# ad.net
KiCad netlist of a schematic drawn in Altium Designer
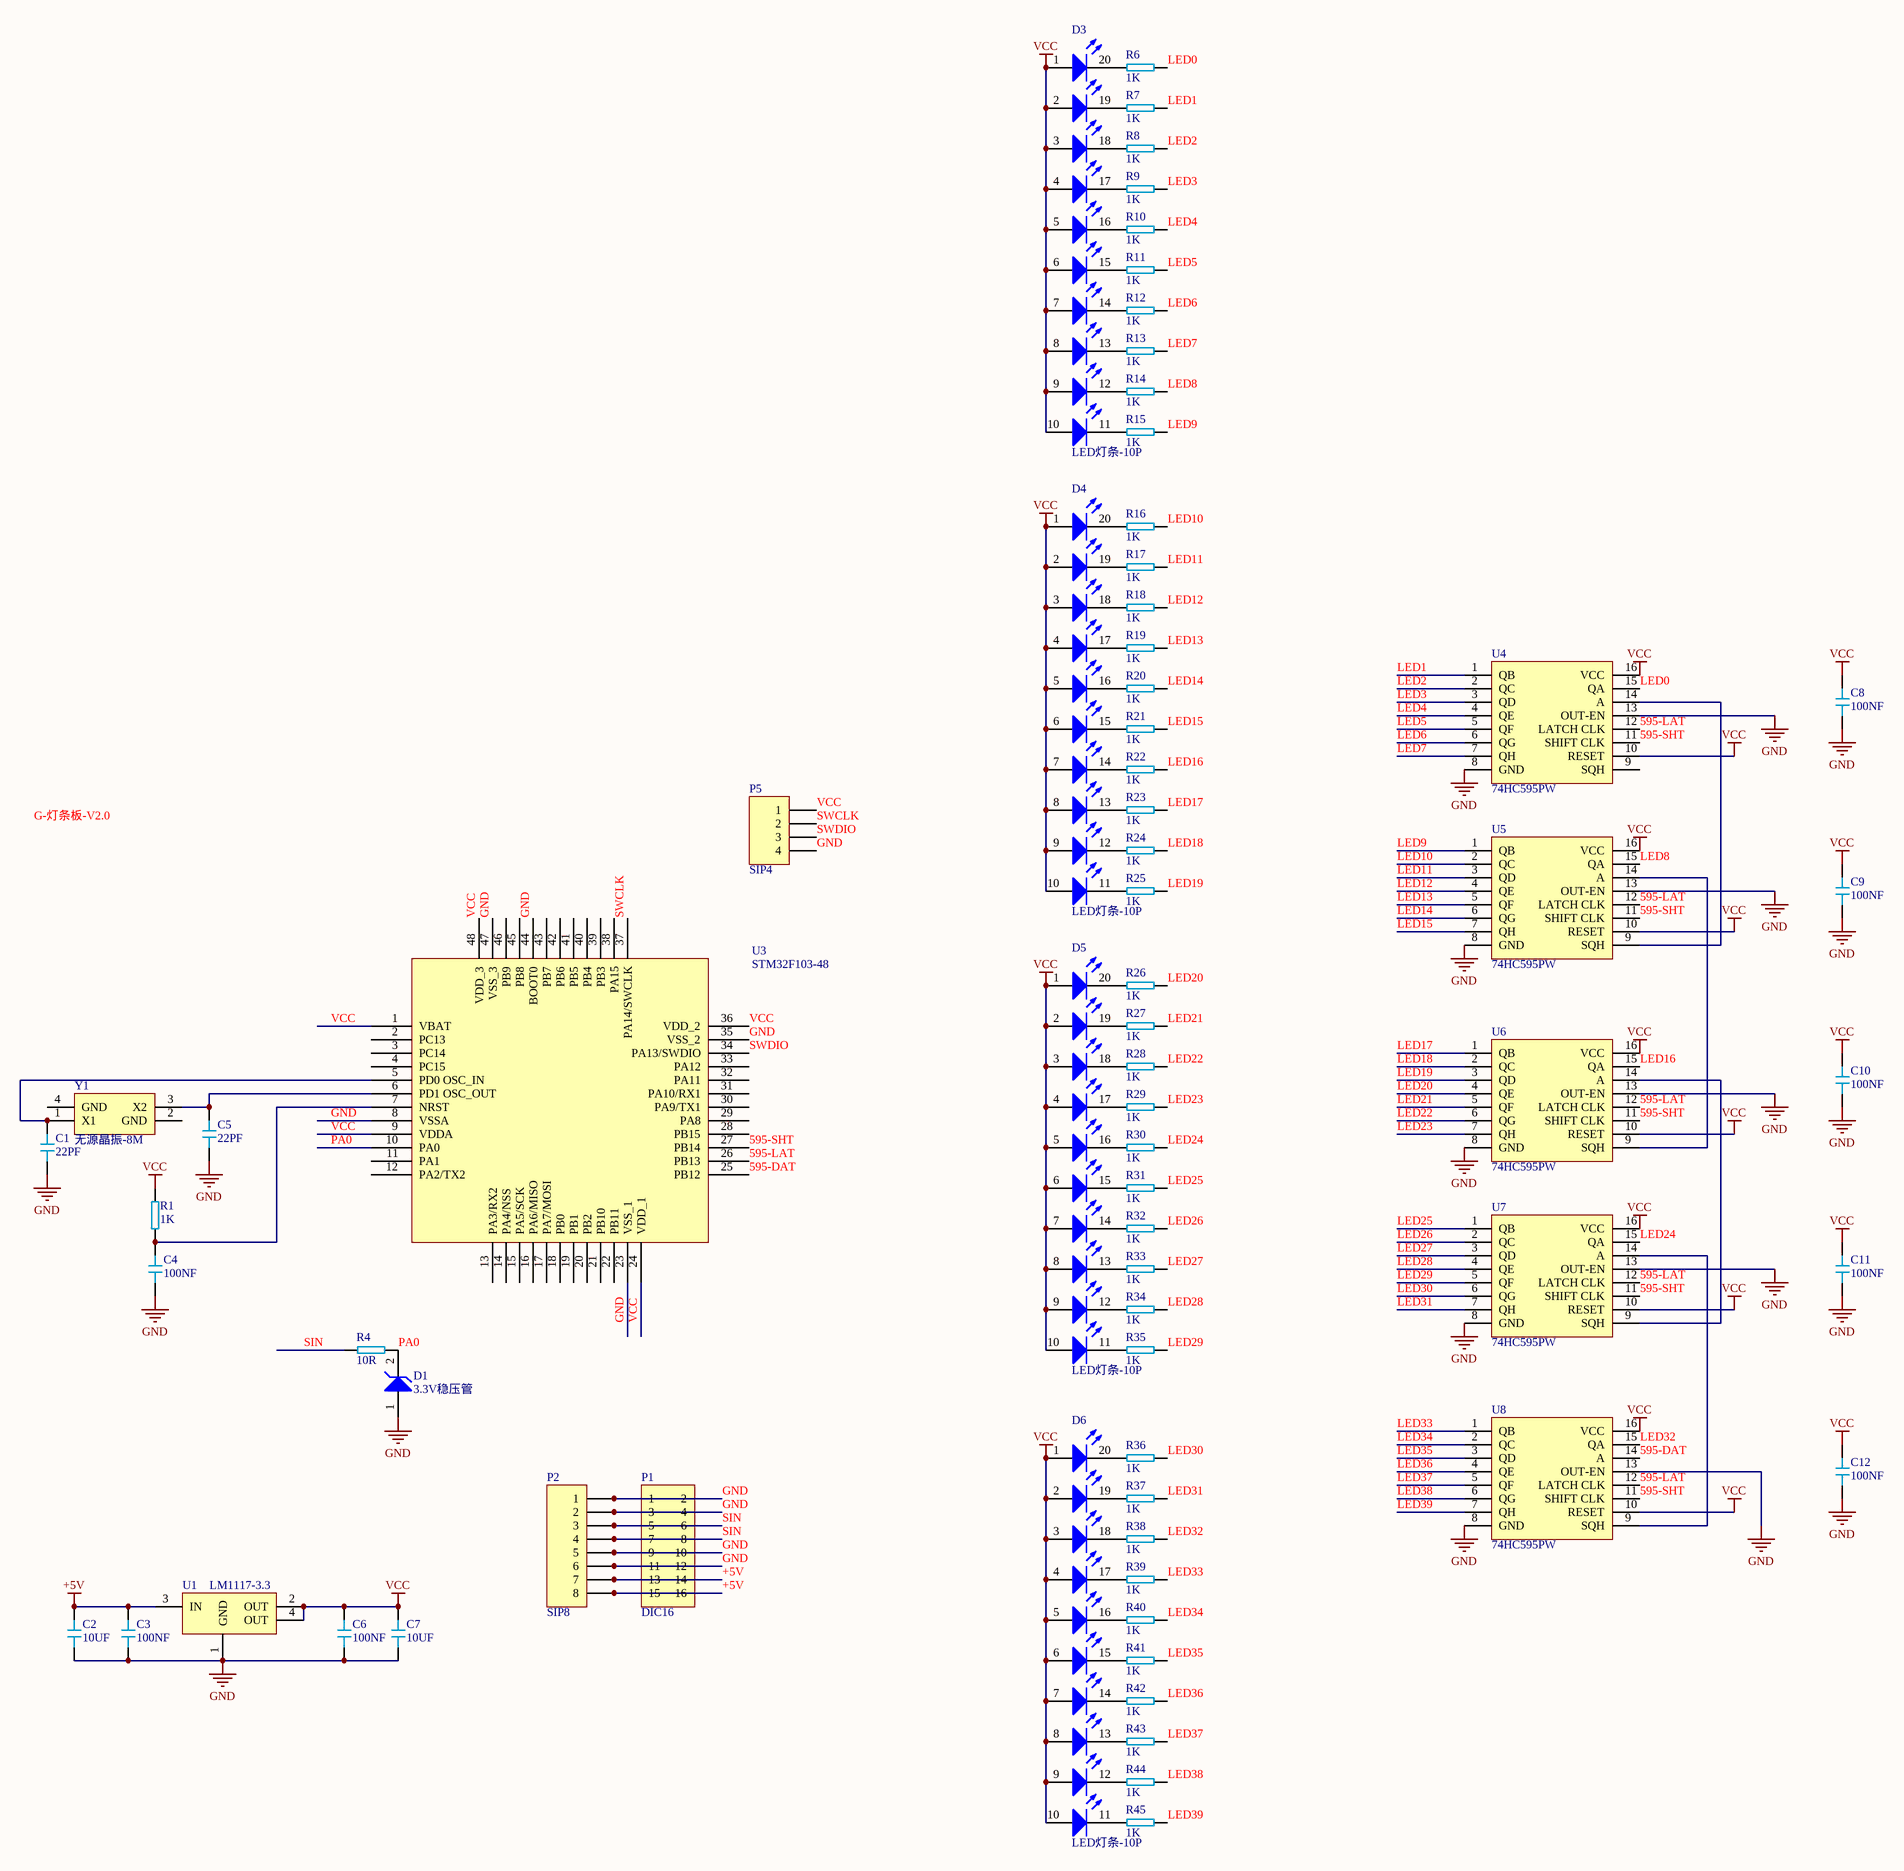
[diagram p0: ad.SchDoc]

(export (version "E")
  (design (tool "Eeschema 10.0.6"))
  (components
    (comp (ref "C1")
      (value "22PF")
      (footprint "C0603")
      (description "贴片电容")
      (libsource (lib "base") (part "C0603"))
    )
    (comp (ref "C2")
      (value "10UF")
      (footprint "C0603")
      (description "贴片电容")
      (libsource (lib "base") (part "C0603"))
    )
    (comp (ref "C3")
      (value "100NF")
      (footprint "C0603")
      (description "贴片电容")
      (libsource (lib "base") (part "C0603"))
    )
    (comp (ref "C4")
      (value "100NF")
      (footprint "C0603")
      (description "贴片电容")
      (libsource (lib "base") (part "C0603"))
    )
    (comp (ref "C5")
      (value "22PF")
      (footprint "C0603")
      (description "贴片电容")
      (libsource (lib "base") (part "C0603"))
    )
    (comp (ref "C6")
      (value "100NF")
      (footprint "C0603")
      (description "贴片电容")
      (libsource (lib "base") (part "C0603"))
    )
    (comp (ref "C7")
      (value "10UF")
      (footprint "C0603")
      (description "贴片电容")
      (libsource (lib "base") (part "C0603"))
    )
    (comp (ref "C8")
      (value "100NF")
      (footprint "C0603")
      (description "贴片电容")
      (libsource (lib "base") (part "C0603"))
    )
    (comp (ref "C9")
      (value "100NF")
      (footprint "C0603")
      (description "贴片电容")
      (libsource (lib "base") (part "C0603"))
    )
    (comp (ref "C10")
      (value "100NF")
      (footprint "C0603")
      (description "贴片电容")
      (libsource (lib "base") (part "C0603"))
    )
    (comp (ref "C11")
      (value "100NF")
      (footprint "C0603")
      (description "贴片电容")
      (libsource (lib "base") (part "C0603"))
    )
    (comp (ref "C12")
      (value "100NF")
      (footprint "C0603")
      (description "贴片电容")
      (libsource (lib "base") (part "C0603"))
    )
    (comp (ref "D1")
      (value "3.3V稳压管")
      (footprint "D1206")
      (description "稳压管")
      (fields (field (name "PUBLISHER") "Altium Limited"))
      (libsource (lib "base") (part "TVS-SMA"))
    )
    (comp (ref "D3")
      (value "LED灯条-10P")
      (footprint "LED-10")
      (description "LED灯条")
      (libsource (lib "Chip") (part "LED-10"))
    )
    (comp (ref "D4")
      (value "LED灯条-10P")
      (footprint "LED-10")
      (description "LED灯条")
      (libsource (lib "Chip") (part "LED-10"))
    )
    (comp (ref "D5")
      (value "LED灯条-10P")
      (footprint "LED-10")
      (description "LED灯条")
      (libsource (lib "Chip") (part "LED-10"))
    )
    (comp (ref "D6")
      (value "LED灯条-10P")
      (footprint "LED-10")
      (description "LED灯条")
      (libsource (lib "Chip") (part "LED-10"))
    )
    (comp (ref "P1")
      (value "DIC16")
      (footprint "141V-8P")
      (description "连接器")
      (fields (field (name "PUBLISHER") "Altium Limited"))
      (libsource (lib "base") (part "DIC16"))
    )
    (comp (ref "P2")
      (value "SIP8")
      (footprint "SIP8")
      (description "连接器")
      (fields (field (name "PUBLISHER") "Altium Limited"))
      (libsource (lib "base") (part "SIP8"))
    )
    (comp (ref "P5")
      (value "SIP4")
      (footprint "SIP4")
      (description "连接器")
      (fields (field (name "PUBLISHER") "Altium Limited"))
      (libsource (lib "base") (part "SIP4"))
    )
    (comp (ref "R1")
      (value "1K")
      (footprint "R0603")
      (description "贴片电阻")
      (libsource (lib "base") (part "R-0603"))
    )
    (comp (ref "R4")
      (value "10R")
      (footprint "R0603")
      (description "贴片电阻")
      (libsource (lib "base") (part "R-0603"))
    )
    (comp (ref "R6")
      (value "1K")
      (footprint "R0603")
      (description "贴片电阻")
      (libsource (lib "base") (part "R-0603"))
    )
    (comp (ref "R7")
      (value "1K")
      (footprint "R0603")
      (description "贴片电阻")
      (libsource (lib "base") (part "R-0603"))
    )
    (comp (ref "R8")
      (value "1K")
      (footprint "R0603")
      (description "贴片电阻")
      (libsource (lib "base") (part "R-0603"))
    )
    (comp (ref "R9")
      (value "1K")
      (footprint "R0603")
      (description "贴片电阻")
      (libsource (lib "base") (part "R-0603"))
    )
    (comp (ref "R10")
      (value "1K")
      (footprint "R0603")
      (description "贴片电阻")
      (libsource (lib "base") (part "R-0603"))
    )
    (comp (ref "R11")
      (value "1K")
      (footprint "R0603")
      (description "贴片电阻")
      (libsource (lib "base") (part "R-0603"))
    )
    (comp (ref "R12")
      (value "1K")
      (footprint "R0603")
      (description "贴片电阻")
      (libsource (lib "base") (part "R-0603"))
    )
    (comp (ref "R13")
      (value "1K")
      (footprint "R0603")
      (description "贴片电阻")
      (libsource (lib "base") (part "R-0603"))
    )
    (comp (ref "R14")
      (value "1K")
      (footprint "R0603")
      (description "贴片电阻")
      (libsource (lib "base") (part "R-0603"))
    )
    (comp (ref "R15")
      (value "1K")
      (footprint "R0603")
      (description "贴片电阻")
      (libsource (lib "base") (part "R-0603"))
    )
    (comp (ref "R16")
      (value "1K")
      (footprint "R0603")
      (description "贴片电阻")
      (libsource (lib "base") (part "R-0603"))
    )
    (comp (ref "R17")
      (value "1K")
      (footprint "R0603")
      (description "贴片电阻")
      (libsource (lib "base") (part "R-0603"))
    )
    (comp (ref "R18")
      (value "1K")
      (footprint "R0603")
      (description "贴片电阻")
      (libsource (lib "base") (part "R-0603"))
    )
    (comp (ref "R19")
      (value "1K")
      (footprint "R0603")
      (description "贴片电阻")
      (libsource (lib "base") (part "R-0603"))
    )
    (comp (ref "R20")
      (value "1K")
      (footprint "R0603")
      (description "贴片电阻")
      (libsource (lib "base") (part "R-0603"))
    )
    (comp (ref "R21")
      (value "1K")
      (footprint "R0603")
      (description "贴片电阻")
      (libsource (lib "base") (part "R-0603"))
    )
    (comp (ref "R22")
      (value "1K")
      (footprint "R0603")
      (description "贴片电阻")
      (libsource (lib "base") (part "R-0603"))
    )
    (comp (ref "R23")
      (value "1K")
      (footprint "R0603")
      (description "贴片电阻")
      (libsource (lib "base") (part "R-0603"))
    )
    (comp (ref "R24")
      (value "1K")
      (footprint "R0603")
      (description "贴片电阻")
      (libsource (lib "base") (part "R-0603"))
    )
    (comp (ref "R25")
      (value "1K")
      (footprint "R0603")
      (description "贴片电阻")
      (libsource (lib "base") (part "R-0603"))
    )
    (comp (ref "R26")
      (value "1K")
      (footprint "R0603")
      (description "贴片电阻")
      (libsource (lib "base") (part "R-0603"))
    )
    (comp (ref "R27")
      (value "1K")
      (footprint "R0603")
      (description "贴片电阻")
      (libsource (lib "base") (part "R-0603"))
    )
    (comp (ref "R28")
      (value "1K")
      (footprint "R0603")
      (description "贴片电阻")
      (libsource (lib "base") (part "R-0603"))
    )
    (comp (ref "R29")
      (value "1K")
      (footprint "R0603")
      (description "贴片电阻")
      (libsource (lib "base") (part "R-0603"))
    )
    (comp (ref "R30")
      (value "1K")
      (footprint "R0603")
      (description "贴片电阻")
      (libsource (lib "base") (part "R-0603"))
    )
    (comp (ref "R31")
      (value "1K")
      (footprint "R0603")
      (description "贴片电阻")
      (libsource (lib "base") (part "R-0603"))
    )
    (comp (ref "R32")
      (value "1K")
      (footprint "R0603")
      (description "贴片电阻")
      (libsource (lib "base") (part "R-0603"))
    )
    (comp (ref "R33")
      (value "1K")
      (footprint "R0603")
      (description "贴片电阻")
      (libsource (lib "base") (part "R-0603"))
    )
    (comp (ref "R34")
      (value "1K")
      (footprint "R0603")
      (description "贴片电阻")
      (libsource (lib "base") (part "R-0603"))
    )
    (comp (ref "R35")
      (value "1K")
      (footprint "R0603")
      (description "贴片电阻")
      (libsource (lib "base") (part "R-0603"))
    )
    (comp (ref "R36")
      (value "1K")
      (footprint "R0603")
      (description "贴片电阻")
      (libsource (lib "base") (part "R-0603"))
    )
    (comp (ref "R37")
      (value "1K")
      (footprint "R0603")
      (description "贴片电阻")
      (libsource (lib "base") (part "R-0603"))
    )
    (comp (ref "R38")
      (value "1K")
      (footprint "R0603")
      (description "贴片电阻")
      (libsource (lib "base") (part "R-0603"))
    )
    (comp (ref "R39")
      (value "1K")
      (footprint "R0603")
      (description "贴片电阻")
      (libsource (lib "base") (part "R-0603"))
    )
    (comp (ref "R40")
      (value "1K")
      (footprint "R0603")
      (description "贴片电阻")
      (libsource (lib "base") (part "R-0603"))
    )
    (comp (ref "R41")
      (value "1K")
      (footprint "R0603")
      (description "贴片电阻")
      (libsource (lib "base") (part "R-0603"))
    )
    (comp (ref "R42")
      (value "1K")
      (footprint "R0603")
      (description "贴片电阻")
      (libsource (lib "base") (part "R-0603"))
    )
    (comp (ref "R43")
      (value "1K")
      (footprint "R0603")
      (description "贴片电阻")
      (libsource (lib "base") (part "R-0603"))
    )
    (comp (ref "R44")
      (value "1K")
      (footprint "R0603")
      (description "贴片电阻")
      (libsource (lib "base") (part "R-0603"))
    )
    (comp (ref "R45")
      (value "1K")
      (footprint "R0603")
      (description "贴片电阻")
      (libsource (lib "base") (part "R-0603"))
    )
    (comp (ref "U1")
      (value "LM1117-3.3")
      (footprint "SOT223")
      (description "芯片")
      (fields (field (name "PUBLISHER") "Altium Limited"))
      (libsource (lib "base") (part "1117"))
    )
    (comp (ref "U3")
      (value "STM32F103-48")
      (footprint "LQFP48")
      (libsource (lib "Chip") (part "STM32F103-48"))
    )
    (comp (ref "U4")
      (value "74HC595PW")
      (footprint "TSSOP16")
      (description "芯片")
      (libsource (lib "Chip") (part "74HC595"))
    )
    (comp (ref "U5")
      (value "74HC595PW")
      (footprint "TSSOP16")
      (description "芯片")
      (libsource (lib "Chip") (part "74HC595"))
    )
    (comp (ref "U6")
      (value "74HC595PW")
      (footprint "TSSOP16")
      (description "芯片")
      (libsource (lib "Chip") (part "74HC595"))
    )
    (comp (ref "U7")
      (value "74HC595PW")
      (footprint "TSSOP16")
      (description "芯片")
      (libsource (lib "Chip") (part "74HC595"))
    )
    (comp (ref "U8")
      (value "74HC595PW")
      (footprint "TSSOP16")
      (description "芯片")
      (libsource (lib "Chip") (part "74HC595"))
    )
    (comp (ref "Y1")
      (value "无源晶振-8M")
      (footprint "XTAL-3225-4")
      (fields (field (name "PUBLISHER") "Altium Limited"))
      (libsource (lib "base") (part "XTAL-4-W"))
    )
  )
  (nets
    (net (code "1") (name "+5V") (class "Default")
      (node (ref "C2") (pin "2") (pinfunction "2_2") (pintype "passive"))
      (node (ref "C3") (pin "2") (pinfunction "2_2") (pintype "passive"))
      (node (ref "P1") (pin "13") (pinfunction "13_13") (pintype "passive"))
      (node (ref "P1") (pin "14") (pinfunction "14_14") (pintype "passive"))
      (node (ref "P1") (pin "15") (pinfunction "15_15") (pintype "passive"))
      (node (ref "P1") (pin "16") (pinfunction "16_16") (pintype "passive"))
      (node (ref "P2") (pin "7") (pinfunction "7_7") (pintype "passive"))
      (node (ref "P2") (pin "8") (pinfunction "8_8") (pintype "passive"))
      (node (ref "U1") (pin "3") (pinfunction "IN_3") (pintype "passive"))
    )
    (net (code "2") (name "/595-DAT") (class "Default")
      (node (ref "U3") (pin "25") (pinfunction "PB12_25") (pintype "passive"))
      (node (ref "U8") (pin "14") (pinfunction "A_14") (pintype "passive"))
    )
    (net (code "3") (name "/595-LAT") (class "Default")
      (node (ref "U3") (pin "26") (pinfunction "PB13_26") (pintype "passive"))
      (node (ref "U4") (pin "12") (pinfunction "LATCH_CLK_12") (pintype "passive"))
      (node (ref "U5") (pin "12") (pinfunction "LATCH_CLK_12") (pintype "passive"))
      (node (ref "U6") (pin "12") (pinfunction "LATCH_CLK_12") (pintype "passive"))
      (node (ref "U7") (pin "12") (pinfunction "LATCH_CLK_12") (pintype "passive"))
      (node (ref "U8") (pin "12") (pinfunction "LATCH_CLK_12") (pintype "passive"))
    )
    (net (code "4") (name "/595-SHT") (class "Default")
      (node (ref "U3") (pin "27") (pinfunction "PB14_27") (pintype "passive"))
      (node (ref "U4") (pin "11") (pinfunction "SHIFT_CLK_11") (pintype "passive"))
      (node (ref "U5") (pin "11") (pinfunction "SHIFT_CLK_11") (pintype "passive"))
      (node (ref "U6") (pin "11") (pinfunction "SHIFT_CLK_11") (pintype "passive"))
      (node (ref "U7") (pin "11") (pinfunction "SHIFT_CLK_11") (pintype "passive"))
      (node (ref "U8") (pin "11") (pinfunction "SHIFT_CLK_11") (pintype "passive"))
    )
    (net (code "6") (name "/LED0") (class "Default")
      (node (ref "R6") (pin "1") (pinfunction "1_1") (pintype "passive"))
      (node (ref "U4") (pin "15") (pinfunction "QA_15") (pintype "passive"))
    )
    (net (code "7") (name "/LED1") (class "Default")
      (node (ref "R7") (pin "1") (pinfunction "1_1") (pintype "passive"))
      (node (ref "U4") (pin "1") (pinfunction "QB_1") (pintype "passive"))
    )
    (net (code "8") (name "/LED2") (class "Default")
      (node (ref "R8") (pin "1") (pinfunction "1_1") (pintype "passive"))
      (node (ref "U4") (pin "2") (pinfunction "QC_2") (pintype "passive"))
    )
    (net (code "9") (name "/LED3") (class "Default")
      (node (ref "R9") (pin "1") (pinfunction "1_1") (pintype "passive"))
      (node (ref "U4") (pin "3") (pinfunction "QD_3") (pintype "passive"))
    )
    (net (code "10") (name "/LED4") (class "Default")
      (node (ref "R10") (pin "1") (pinfunction "1_1") (pintype "passive"))
      (node (ref "U4") (pin "4") (pinfunction "QE_4") (pintype "passive"))
    )
    (net (code "11") (name "/LED5") (class "Default")
      (node (ref "R11") (pin "1") (pinfunction "1_1") (pintype "passive"))
      (node (ref "U4") (pin "5") (pinfunction "QF_5") (pintype "passive"))
    )
    (net (code "12") (name "/LED6") (class "Default")
      (node (ref "R12") (pin "1") (pinfunction "1_1") (pintype "passive"))
      (node (ref "U4") (pin "6") (pinfunction "QG_6") (pintype "passive"))
    )
    (net (code "13") (name "/LED7") (class "Default")
      (node (ref "R13") (pin "1") (pinfunction "1_1") (pintype "passive"))
      (node (ref "U4") (pin "7") (pinfunction "QH_7") (pintype "passive"))
    )
    (net (code "14") (name "/LED8") (class "Default")
      (node (ref "R14") (pin "1") (pinfunction "1_1") (pintype "passive"))
      (node (ref "U5") (pin "15") (pinfunction "QA_15") (pintype "passive"))
    )
    (net (code "15") (name "/LED9") (class "Default")
      (node (ref "R15") (pin "1") (pinfunction "1_1") (pintype "passive"))
      (node (ref "U5") (pin "1") (pinfunction "QB_1") (pintype "passive"))
    )
    (net (code "16") (name "/LED10") (class "Default")
      (node (ref "R16") (pin "1") (pinfunction "1_1") (pintype "passive"))
      (node (ref "U5") (pin "2") (pinfunction "QC_2") (pintype "passive"))
    )
    (net (code "17") (name "/LED11") (class "Default")
      (node (ref "R17") (pin "1") (pinfunction "1_1") (pintype "passive"))
      (node (ref "U5") (pin "3") (pinfunction "QD_3") (pintype "passive"))
    )
    (net (code "18") (name "/LED12") (class "Default")
      (node (ref "R18") (pin "1") (pinfunction "1_1") (pintype "passive"))
      (node (ref "U5") (pin "4") (pinfunction "QE_4") (pintype "passive"))
    )
    (net (code "19") (name "/LED13") (class "Default")
      (node (ref "R19") (pin "1") (pinfunction "1_1") (pintype "passive"))
      (node (ref "U5") (pin "5") (pinfunction "QF_5") (pintype "passive"))
    )
    (net (code "20") (name "/LED14") (class "Default")
      (node (ref "R20") (pin "1") (pinfunction "1_1") (pintype "passive"))
      (node (ref "U5") (pin "6") (pinfunction "QG_6") (pintype "passive"))
    )
    (net (code "21") (name "/LED15") (class "Default")
      (node (ref "R21") (pin "1") (pinfunction "1_1") (pintype "passive"))
      (node (ref "U5") (pin "7") (pinfunction "QH_7") (pintype "passive"))
    )
    (net (code "22") (name "/LED16") (class "Default")
      (node (ref "R22") (pin "1") (pinfunction "1_1") (pintype "passive"))
      (node (ref "U6") (pin "15") (pinfunction "QA_15") (pintype "passive"))
    )
    (net (code "23") (name "/LED17") (class "Default")
      (node (ref "R23") (pin "1") (pinfunction "1_1") (pintype "passive"))
      (node (ref "U6") (pin "1") (pinfunction "QB_1") (pintype "passive"))
    )
    (net (code "24") (name "/LED18") (class "Default")
      (node (ref "R24") (pin "1") (pinfunction "1_1") (pintype "passive"))
      (node (ref "U6") (pin "2") (pinfunction "QC_2") (pintype "passive"))
    )
    (net (code "25") (name "/LED19") (class "Default")
      (node (ref "R25") (pin "1") (pinfunction "1_1") (pintype "passive"))
      (node (ref "U6") (pin "3") (pinfunction "QD_3") (pintype "passive"))
    )
    (net (code "26") (name "/LED20") (class "Default")
      (node (ref "R26") (pin "1") (pinfunction "1_1") (pintype "passive"))
      (node (ref "U6") (pin "4") (pinfunction "QE_4") (pintype "passive"))
    )
    (net (code "27") (name "/LED21") (class "Default")
      (node (ref "R27") (pin "1") (pinfunction "1_1") (pintype "passive"))
      (node (ref "U6") (pin "5") (pinfunction "QF_5") (pintype "passive"))
    )
    (net (code "28") (name "/LED22") (class "Default")
      (node (ref "R28") (pin "1") (pinfunction "1_1") (pintype "passive"))
      (node (ref "U6") (pin "6") (pinfunction "QG_6") (pintype "passive"))
    )
    (net (code "29") (name "/LED23") (class "Default")
      (node (ref "R29") (pin "1") (pinfunction "1_1") (pintype "passive"))
      (node (ref "U6") (pin "7") (pinfunction "QH_7") (pintype "passive"))
    )
    (net (code "30") (name "/LED24") (class "Default")
      (node (ref "R30") (pin "1") (pinfunction "1_1") (pintype "passive"))
      (node (ref "U7") (pin "15") (pinfunction "QA_15") (pintype "passive"))
    )
    (net (code "31") (name "/LED25") (class "Default")
      (node (ref "R31") (pin "1") (pinfunction "1_1") (pintype "passive"))
      (node (ref "U7") (pin "1") (pinfunction "QB_1") (pintype "passive"))
    )
    (net (code "32") (name "/LED26") (class "Default")
      (node (ref "R32") (pin "1") (pinfunction "1_1") (pintype "passive"))
      (node (ref "U7") (pin "2") (pinfunction "QC_2") (pintype "passive"))
    )
    (net (code "33") (name "/LED27") (class "Default")
      (node (ref "R33") (pin "1") (pinfunction "1_1") (pintype "passive"))
      (node (ref "U7") (pin "3") (pinfunction "QD_3") (pintype "passive"))
    )
    (net (code "34") (name "/LED28") (class "Default")
      (node (ref "R34") (pin "1") (pinfunction "1_1") (pintype "passive"))
      (node (ref "U7") (pin "4") (pinfunction "QE_4") (pintype "passive"))
    )
    (net (code "35") (name "/LED29") (class "Default")
      (node (ref "R35") (pin "1") (pinfunction "1_1") (pintype "passive"))
      (node (ref "U7") (pin "5") (pinfunction "QF_5") (pintype "passive"))
    )
    (net (code "36") (name "/LED30") (class "Default")
      (node (ref "R36") (pin "1") (pinfunction "1_1") (pintype "passive"))
      (node (ref "U7") (pin "6") (pinfunction "QG_6") (pintype "passive"))
    )
    (net (code "37") (name "/LED31") (class "Default")
      (node (ref "R37") (pin "1") (pinfunction "1_1") (pintype "passive"))
      (node (ref "U7") (pin "7") (pinfunction "QH_7") (pintype "passive"))
    )
    (net (code "38") (name "/LED32") (class "Default")
      (node (ref "R38") (pin "1") (pinfunction "1_1") (pintype "passive"))
      (node (ref "U8") (pin "15") (pinfunction "QA_15") (pintype "passive"))
    )
    (net (code "39") (name "/LED33") (class "Default")
      (node (ref "R39") (pin "1") (pinfunction "1_1") (pintype "passive"))
      (node (ref "U8") (pin "1") (pinfunction "QB_1") (pintype "passive"))
    )
    (net (code "40") (name "/LED34") (class "Default")
      (node (ref "R40") (pin "1") (pinfunction "1_1") (pintype "passive"))
      (node (ref "U8") (pin "2") (pinfunction "QC_2") (pintype "passive"))
    )
    (net (code "41") (name "/LED35") (class "Default")
      (node (ref "R41") (pin "1") (pinfunction "1_1") (pintype "passive"))
      (node (ref "U8") (pin "3") (pinfunction "QD_3") (pintype "passive"))
    )
    (net (code "42") (name "/LED36") (class "Default")
      (node (ref "R42") (pin "1") (pinfunction "1_1") (pintype "passive"))
      (node (ref "U8") (pin "4") (pinfunction "QE_4") (pintype "passive"))
    )
    (net (code "43") (name "/LED37") (class "Default")
      (node (ref "R43") (pin "1") (pinfunction "1_1") (pintype "passive"))
      (node (ref "U8") (pin "5") (pinfunction "QF_5") (pintype "passive"))
    )
    (net (code "44") (name "/LED38") (class "Default")
      (node (ref "R44") (pin "1") (pinfunction "1_1") (pintype "passive"))
      (node (ref "U8") (pin "6") (pinfunction "QG_6") (pintype "passive"))
    )
    (net (code "45") (name "/LED39") (class "Default")
      (node (ref "R45") (pin "1") (pinfunction "1_1") (pintype "passive"))
      (node (ref "U8") (pin "7") (pinfunction "QH_7") (pintype "passive"))
    )
    (net (code "46") (name "/PA0") (class "Default")
      (node (ref "D1") (pin "2") (pinfunction "2_2") (pintype "passive"))
      (node (ref "R4") (pin "2") (pinfunction "2_2") (pintype "passive"))
      (node (ref "U3") (pin "10") (pinfunction "PA0_10") (pintype "passive"))
    )
    (net (code "47") (name "/SIN") (class "Default")
      (node (ref "P1") (pin "5") (pinfunction "5_5") (pintype "passive"))
      (node (ref "P1") (pin "6") (pinfunction "6_6") (pintype "passive"))
      (node (ref "P1") (pin "7") (pinfunction "7_7") (pintype "passive"))
      (node (ref "P1") (pin "8") (pinfunction "8_8") (pintype "passive"))
      (node (ref "P2") (pin "3") (pinfunction "3_3") (pintype "passive"))
      (node (ref "P2") (pin "4") (pinfunction "4_4") (pintype "passive"))
      (node (ref "R4") (pin "1") (pinfunction "1_1") (pintype "passive"))
    )
    (net (code "48") (name "/SWCLK") (class "Default")
      (node (ref "P5") (pin "2") (pinfunction "2_2") (pintype "passive"))
      (node (ref "U3") (pin "37") (pinfunction "PA14/SWCLK_37") (pintype "passive"))
    )
    (net (code "49") (name "/SWDIO") (class "Default")
      (node (ref "P5") (pin "3") (pinfunction "3_3") (pintype "passive"))
      (node (ref "U3") (pin "34") (pinfunction "PA13/SWDIO_34") (pintype "passive"))
    )
    (net (code "50") (name "GND") (class "Default")
      (node (ref "C1") (pin "1") (pinfunction "1_1") (pintype "passive"))
      (node (ref "C10") (pin "1") (pinfunction "1_1") (pintype "passive"))
      (node (ref "C11") (pin "1") (pinfunction "1_1") (pintype "passive"))
      (node (ref "C12") (pin "1") (pinfunction "1_1") (pintype "passive"))
      (node (ref "C2") (pin "1") (pinfunction "1_1") (pintype "passive"))
      (node (ref "C3") (pin "1") (pinfunction "1_1") (pintype "passive"))
      (node (ref "C4") (pin "1") (pinfunction "1_1") (pintype "passive"))
      (node (ref "C5") (pin "1") (pinfunction "1_1") (pintype "passive"))
      (node (ref "C6") (pin "1") (pinfunction "1_1") (pintype "passive"))
      (node (ref "C7") (pin "1") (pinfunction "1_1") (pintype "passive"))
      (node (ref "C8") (pin "1") (pinfunction "1_1") (pintype "passive"))
      (node (ref "C9") (pin "1") (pinfunction "1_1") (pintype "passive"))
      (node (ref "D1") (pin "1") (pinfunction "1_1") (pintype "passive"))
      (node (ref "P1") (pin "1") (pinfunction "1_1") (pintype "passive"))
      (node (ref "P1") (pin "10") (pinfunction "10_10") (pintype "passive"))
      (node (ref "P1") (pin "11") (pinfunction "11_11") (pintype "passive"))
      (node (ref "P1") (pin "12") (pinfunction "12_12") (pintype "passive"))
      (node (ref "P1") (pin "2") (pinfunction "2_2") (pintype "passive"))
      (node (ref "P1") (pin "3") (pinfunction "3_3") (pintype "passive"))
      (node (ref "P1") (pin "4") (pinfunction "4_4") (pintype "passive"))
      (node (ref "P1") (pin "9") (pinfunction "9_9") (pintype "passive"))
      (node (ref "P2") (pin "1") (pinfunction "1_1") (pintype "passive"))
      (node (ref "P2") (pin "2") (pinfunction "2_2") (pintype "passive"))
      (node (ref "P2") (pin "5") (pinfunction "5_5") (pintype "passive"))
      (node (ref "P2") (pin "6") (pinfunction "6_6") (pintype "passive"))
      (node (ref "P5") (pin "4") (pinfunction "4_4") (pintype "passive"))
      (node (ref "U1") (pin "1") (pinfunction "GND_1") (pintype "passive"))
      (node (ref "U3") (pin "23") (pinfunction "VSS_1_23") (pintype "passive"))
      (node (ref "U3") (pin "35") (pinfunction "VSS_2_35") (pintype "passive"))
      (node (ref "U3") (pin "44") (pinfunction "BOOT0_44") (pintype "passive"))
      (node (ref "U3") (pin "47") (pinfunction "VSS_3_47") (pintype "passive"))
      (node (ref "U3") (pin "8") (pinfunction "VSSA_8") (pintype "passive"))
      (node (ref "U4") (pin "13") (pinfunction "OUT-EN_13") (pintype "passive"))
      (node (ref "U4") (pin "8") (pinfunction "GND_8") (pintype "passive"))
      (node (ref "U5") (pin "13") (pinfunction "OUT-EN_13") (pintype "passive"))
      (node (ref "U5") (pin "8") (pinfunction "GND_8") (pintype "passive"))
      (node (ref "U6") (pin "13") (pinfunction "OUT-EN_13") (pintype "passive"))
      (node (ref "U6") (pin "8") (pinfunction "GND_8") (pintype "passive"))
      (node (ref "U7") (pin "13") (pinfunction "OUT-EN_13") (pintype "passive"))
      (node (ref "U7") (pin "8") (pinfunction "GND_8") (pintype "passive"))
      (node (ref "U8") (pin "13") (pinfunction "OUT-EN_13") (pintype "passive"))
      (node (ref "U8") (pin "8") (pinfunction "GND_8") (pintype "passive"))
    )
    (net (code "51") (name "Net-(D3-K-Pad11)") (class "Default")
      (node (ref "D3") (pin "11") (pinfunction "K_11") (pintype "passive"))
      (node (ref "R15") (pin "2") (pinfunction "2_2") (pintype "passive"))
    )
    (net (code "52") (name "Net-(D3-K-Pad12)") (class "Default")
      (node (ref "D3") (pin "12") (pinfunction "K_12") (pintype "passive"))
      (node (ref "R14") (pin "2") (pinfunction "2_2") (pintype "passive"))
    )
    (net (code "53") (name "Net-(D3-K-Pad13)") (class "Default")
      (node (ref "D3") (pin "13") (pinfunction "K_13") (pintype "passive"))
      (node (ref "R13") (pin "2") (pinfunction "2_2") (pintype "passive"))
    )
    (net (code "54") (name "Net-(D3-K-Pad14)") (class "Default")
      (node (ref "D3") (pin "14") (pinfunction "K_14") (pintype "passive"))
      (node (ref "R12") (pin "2") (pinfunction "2_2") (pintype "passive"))
    )
    (net (code "55") (name "Net-(D3-K-Pad15)") (class "Default")
      (node (ref "D3") (pin "15") (pinfunction "K_15") (pintype "passive"))
      (node (ref "R11") (pin "2") (pinfunction "2_2") (pintype "passive"))
    )
    (net (code "56") (name "Net-(D3-K-Pad16)") (class "Default")
      (node (ref "D3") (pin "16") (pinfunction "K_16") (pintype "passive"))
      (node (ref "R10") (pin "2") (pinfunction "2_2") (pintype "passive"))
    )
    (net (code "57") (name "Net-(D3-K-Pad17)") (class "Default")
      (node (ref "D3") (pin "17") (pinfunction "K_17") (pintype "passive"))
      (node (ref "R9") (pin "2") (pinfunction "2_2") (pintype "passive"))
    )
    (net (code "58") (name "Net-(D3-K-Pad18)") (class "Default")
      (node (ref "D3") (pin "18") (pinfunction "K_18") (pintype "passive"))
      (node (ref "R8") (pin "2") (pinfunction "2_2") (pintype "passive"))
    )
    (net (code "59") (name "Net-(D3-K-Pad19)") (class "Default")
      (node (ref "D3") (pin "19") (pinfunction "K_19") (pintype "passive"))
      (node (ref "R7") (pin "2") (pinfunction "2_2") (pintype "passive"))
    )
    (net (code "60") (name "Net-(D3-K-Pad20)") (class "Default")
      (node (ref "D3") (pin "20") (pinfunction "K_20") (pintype "passive"))
      (node (ref "R6") (pin "2") (pinfunction "2_2") (pintype "passive"))
    )
    (net (code "61") (name "Net-(D4-K-Pad11)") (class "Default")
      (node (ref "D4") (pin "11") (pinfunction "K_11") (pintype "passive"))
      (node (ref "R25") (pin "2") (pinfunction "2_2") (pintype "passive"))
    )
    (net (code "62") (name "Net-(D4-K-Pad12)") (class "Default")
      (node (ref "D4") (pin "12") (pinfunction "K_12") (pintype "passive"))
      (node (ref "R24") (pin "2") (pinfunction "2_2") (pintype "passive"))
    )
    (net (code "63") (name "Net-(D4-K-Pad13)") (class "Default")
      (node (ref "D4") (pin "13") (pinfunction "K_13") (pintype "passive"))
      (node (ref "R23") (pin "2") (pinfunction "2_2") (pintype "passive"))
    )
    (net (code "64") (name "Net-(D4-K-Pad14)") (class "Default")
      (node (ref "D4") (pin "14") (pinfunction "K_14") (pintype "passive"))
      (node (ref "R22") (pin "2") (pinfunction "2_2") (pintype "passive"))
    )
    (net (code "65") (name "Net-(D4-K-Pad15)") (class "Default")
      (node (ref "D4") (pin "15") (pinfunction "K_15") (pintype "passive"))
      (node (ref "R21") (pin "2") (pinfunction "2_2") (pintype "passive"))
    )
    (net (code "66") (name "Net-(D4-K-Pad16)") (class "Default")
      (node (ref "D4") (pin "16") (pinfunction "K_16") (pintype "passive"))
      (node (ref "R20") (pin "2") (pinfunction "2_2") (pintype "passive"))
    )
    (net (code "67") (name "Net-(D4-K-Pad17)") (class "Default")
      (node (ref "D4") (pin "17") (pinfunction "K_17") (pintype "passive"))
      (node (ref "R19") (pin "2") (pinfunction "2_2") (pintype "passive"))
    )
    (net (code "68") (name "Net-(D4-K-Pad18)") (class "Default")
      (node (ref "D4") (pin "18") (pinfunction "K_18") (pintype "passive"))
      (node (ref "R18") (pin "2") (pinfunction "2_2") (pintype "passive"))
    )
    (net (code "69") (name "Net-(D4-K-Pad19)") (class "Default")
      (node (ref "D4") (pin "19") (pinfunction "K_19") (pintype "passive"))
      (node (ref "R17") (pin "2") (pinfunction "2_2") (pintype "passive"))
    )
    (net (code "70") (name "Net-(D4-K-Pad20)") (class "Default")
      (node (ref "D4") (pin "20") (pinfunction "K_20") (pintype "passive"))
      (node (ref "R16") (pin "2") (pinfunction "2_2") (pintype "passive"))
    )
    (net (code "71") (name "Net-(D5-K-Pad11)") (class "Default")
      (node (ref "D5") (pin "11") (pinfunction "K_11") (pintype "passive"))
      (node (ref "R35") (pin "2") (pinfunction "2_2") (pintype "passive"))
    )
    (net (code "72") (name "Net-(D5-K-Pad12)") (class "Default")
      (node (ref "D5") (pin "12") (pinfunction "K_12") (pintype "passive"))
      (node (ref "R34") (pin "2") (pinfunction "2_2") (pintype "passive"))
    )
    (net (code "73") (name "Net-(D5-K-Pad13)") (class "Default")
      (node (ref "D5") (pin "13") (pinfunction "K_13") (pintype "passive"))
      (node (ref "R33") (pin "2") (pinfunction "2_2") (pintype "passive"))
    )
    (net (code "74") (name "Net-(D5-K-Pad14)") (class "Default")
      (node (ref "D5") (pin "14") (pinfunction "K_14") (pintype "passive"))
      (node (ref "R32") (pin "2") (pinfunction "2_2") (pintype "passive"))
    )
    (net (code "75") (name "Net-(D5-K-Pad15)") (class "Default")
      (node (ref "D5") (pin "15") (pinfunction "K_15") (pintype "passive"))
      (node (ref "R31") (pin "2") (pinfunction "2_2") (pintype "passive"))
    )
    (net (code "76") (name "Net-(D5-K-Pad16)") (class "Default")
      (node (ref "D5") (pin "16") (pinfunction "K_16") (pintype "passive"))
      (node (ref "R30") (pin "2") (pinfunction "2_2") (pintype "passive"))
    )
    (net (code "77") (name "Net-(D5-K-Pad17)") (class "Default")
      (node (ref "D5") (pin "17") (pinfunction "K_17") (pintype "passive"))
      (node (ref "R29") (pin "2") (pinfunction "2_2") (pintype "passive"))
    )
    (net (code "78") (name "Net-(D5-K-Pad18)") (class "Default")
      (node (ref "D5") (pin "18") (pinfunction "K_18") (pintype "passive"))
      (node (ref "R28") (pin "2") (pinfunction "2_2") (pintype "passive"))
    )
    (net (code "79") (name "Net-(D5-K-Pad19)") (class "Default")
      (node (ref "D5") (pin "19") (pinfunction "K_19") (pintype "passive"))
      (node (ref "R27") (pin "2") (pinfunction "2_2") (pintype "passive"))
    )
    (net (code "80") (name "Net-(D5-K-Pad20)") (class "Default")
      (node (ref "D5") (pin "20") (pinfunction "K_20") (pintype "passive"))
      (node (ref "R26") (pin "2") (pinfunction "2_2") (pintype "passive"))
    )
    (net (code "81") (name "Net-(D6-K-Pad11)") (class "Default")
      (node (ref "D6") (pin "11") (pinfunction "K_11") (pintype "passive"))
      (node (ref "R45") (pin "2") (pinfunction "2_2") (pintype "passive"))
    )
    (net (code "82") (name "Net-(D6-K-Pad12)") (class "Default")
      (node (ref "D6") (pin "12") (pinfunction "K_12") (pintype "passive"))
      (node (ref "R44") (pin "2") (pinfunction "2_2") (pintype "passive"))
    )
    (net (code "83") (name "Net-(D6-K-Pad13)") (class "Default")
      (node (ref "D6") (pin "13") (pinfunction "K_13") (pintype "passive"))
      (node (ref "R43") (pin "2") (pinfunction "2_2") (pintype "passive"))
    )
    (net (code "84") (name "Net-(D6-K-Pad14)") (class "Default")
      (node (ref "D6") (pin "14") (pinfunction "K_14") (pintype "passive"))
      (node (ref "R42") (pin "2") (pinfunction "2_2") (pintype "passive"))
    )
    (net (code "85") (name "Net-(D6-K-Pad15)") (class "Default")
      (node (ref "D6") (pin "15") (pinfunction "K_15") (pintype "passive"))
      (node (ref "R41") (pin "2") (pinfunction "2_2") (pintype "passive"))
    )
    (net (code "86") (name "Net-(D6-K-Pad16)") (class "Default")
      (node (ref "D6") (pin "16") (pinfunction "K_16") (pintype "passive"))
      (node (ref "R40") (pin "2") (pinfunction "2_2") (pintype "passive"))
    )
    (net (code "87") (name "Net-(D6-K-Pad17)") (class "Default")
      (node (ref "D6") (pin "17") (pinfunction "K_17") (pintype "passive"))
      (node (ref "R39") (pin "2") (pinfunction "2_2") (pintype "passive"))
    )
    (net (code "88") (name "Net-(D6-K-Pad18)") (class "Default")
      (node (ref "D6") (pin "18") (pinfunction "K_18") (pintype "passive"))
      (node (ref "R38") (pin "2") (pinfunction "2_2") (pintype "passive"))
    )
    (net (code "89") (name "Net-(D6-K-Pad19)") (class "Default")
      (node (ref "D6") (pin "19") (pinfunction "K_19") (pintype "passive"))
      (node (ref "R37") (pin "2") (pinfunction "2_2") (pintype "passive"))
    )
    (net (code "90") (name "Net-(D6-K-Pad20)") (class "Default")
      (node (ref "D6") (pin "20") (pinfunction "K_20") (pintype "passive"))
      (node (ref "R36") (pin "2") (pinfunction "2_2") (pintype "passive"))
    )
    (net (code "91") (name "Net-(U3-NRST)") (class "Default")
      (node (ref "C4") (pin "2") (pinfunction "2_2") (pintype "passive"))
      (node (ref "R1") (pin "1") (pinfunction "1_1") (pintype "passive"))
      (node (ref "U3") (pin "7") (pinfunction "NRST_7") (pintype "passive"))
    )
    (net (code "92") (name "Net-(U3-PD0_OSC_IN)") (class "Default")
      (node (ref "C1") (pin "2") (pinfunction "2_2") (pintype "passive"))
      (node (ref "U3") (pin "5") (pinfunction "PD0_OSC_IN_5") (pintype "passive"))
      (node (ref "Y1") (pin "1") (pinfunction "X1_1") (pintype "passive"))
    )
    (net (code "93") (name "Net-(U3-PD1_OSC_OUT)") (class "Default")
      (node (ref "C5") (pin "2") (pinfunction "2_2") (pintype "passive"))
      (node (ref "U3") (pin "6") (pinfunction "PD1_OSC_OUT_6") (pintype "passive"))
      (node (ref "Y1") (pin "3") (pinfunction "X2_3") (pintype "passive"))
    )
    (net (code "94") (name "Net-(U4-A)") (class "Default")
      (node (ref "U4") (pin "14") (pinfunction "A_14") (pintype "passive"))
      (node (ref "U5") (pin "9") (pinfunction "SQH_9") (pintype "passive"))
    )
    (net (code "95") (name "Net-(U5-A)") (class "Default")
      (node (ref "U5") (pin "14") (pinfunction "A_14") (pintype "passive"))
      (node (ref "U6") (pin "9") (pinfunction "SQH_9") (pintype "passive"))
    )
    (net (code "96") (name "Net-(U6-A)") (class "Default")
      (node (ref "U6") (pin "14") (pinfunction "A_14") (pintype "passive"))
      (node (ref "U7") (pin "9") (pinfunction "SQH_9") (pintype "passive"))
    )
    (net (code "97") (name "Net-(U7-A)") (class "Default")
      (node (ref "U7") (pin "14") (pinfunction "A_14") (pintype "passive"))
      (node (ref "U8") (pin "9") (pinfunction "SQH_9") (pintype "passive"))
    )
    (net (code "98") (name "VCC") (class "Default")
      (node (ref "C10") (pin "2") (pinfunction "2_2") (pintype "passive"))
      (node (ref "C11") (pin "2") (pinfunction "2_2") (pintype "passive"))
      (node (ref "C12") (pin "2") (pinfunction "2_2") (pintype "passive"))
      (node (ref "C6") (pin "2") (pinfunction "2_2") (pintype "passive"))
      (node (ref "C7") (pin "2") (pinfunction "2_2") (pintype "passive"))
      (node (ref "C8") (pin "2") (pinfunction "2_2") (pintype "passive"))
      (node (ref "C9") (pin "2") (pinfunction "2_2") (pintype "passive"))
      (node (ref "D3") (pin "1") (pinfunction "A_1") (pintype "passive"))
      (node (ref "D3") (pin "10") (pinfunction "A_10") (pintype "passive"))
      (node (ref "D3") (pin "2") (pinfunction "A_2") (pintype "passive"))
      (node (ref "D3") (pin "3") (pinfunction "A_3") (pintype "passive"))
      (node (ref "D3") (pin "4") (pinfunction "A_4") (pintype "passive"))
      (node (ref "D3") (pin "5") (pinfunction "A_5") (pintype "passive"))
      (node (ref "D3") (pin "6") (pinfunction "A_6") (pintype "passive"))
      (node (ref "D3") (pin "7") (pinfunction "A_7") (pintype "passive"))
      (node (ref "D3") (pin "8") (pinfunction "A_8") (pintype "passive"))
      (node (ref "D3") (pin "9") (pinfunction "A_9") (pintype "passive"))
      (node (ref "D4") (pin "1") (pinfunction "A_1") (pintype "passive"))
      (node (ref "D4") (pin "10") (pinfunction "A_10") (pintype "passive"))
      (node (ref "D4") (pin "2") (pinfunction "A_2") (pintype "passive"))
      (node (ref "D4") (pin "3") (pinfunction "A_3") (pintype "passive"))
      (node (ref "D4") (pin "4") (pinfunction "A_4") (pintype "passive"))
      (node (ref "D4") (pin "5") (pinfunction "A_5") (pintype "passive"))
      (node (ref "D4") (pin "6") (pinfunction "A_6") (pintype "passive"))
      (node (ref "D4") (pin "7") (pinfunction "A_7") (pintype "passive"))
      (node (ref "D4") (pin "8") (pinfunction "A_8") (pintype "passive"))
      (node (ref "D4") (pin "9") (pinfunction "A_9") (pintype "passive"))
      (node (ref "D5") (pin "1") (pinfunction "A_1") (pintype "passive"))
      (node (ref "D5") (pin "10") (pinfunction "A_10") (pintype "passive"))
      (node (ref "D5") (pin "2") (pinfunction "A_2") (pintype "passive"))
      (node (ref "D5") (pin "3") (pinfunction "A_3") (pintype "passive"))
      (node (ref "D5") (pin "4") (pinfunction "A_4") (pintype "passive"))
      (node (ref "D5") (pin "5") (pinfunction "A_5") (pintype "passive"))
      (node (ref "D5") (pin "6") (pinfunction "A_6") (pintype "passive"))
      (node (ref "D5") (pin "7") (pinfunction "A_7") (pintype "passive"))
      (node (ref "D5") (pin "8") (pinfunction "A_8") (pintype "passive"))
      (node (ref "D5") (pin "9") (pinfunction "A_9") (pintype "passive"))
      (node (ref "D6") (pin "1") (pinfunction "A_1") (pintype "passive"))
      (node (ref "D6") (pin "10") (pinfunction "A_10") (pintype "passive"))
      (node (ref "D6") (pin "2") (pinfunction "A_2") (pintype "passive"))
      (node (ref "D6") (pin "3") (pinfunction "A_3") (pintype "passive"))
      (node (ref "D6") (pin "4") (pinfunction "A_4") (pintype "passive"))
      (node (ref "D6") (pin "5") (pinfunction "A_5") (pintype "passive"))
      (node (ref "D6") (pin "6") (pinfunction "A_6") (pintype "passive"))
      (node (ref "D6") (pin "7") (pinfunction "A_7") (pintype "passive"))
      (node (ref "D6") (pin "8") (pinfunction "A_8") (pintype "passive"))
      (node (ref "D6") (pin "9") (pinfunction "A_9") (pintype "passive"))
      (node (ref "P5") (pin "1") (pinfunction "1_1") (pintype "passive"))
      (node (ref "R1") (pin "2") (pinfunction "2_2") (pintype "passive"))
      (node (ref "U1") (pin "2") (pinfunction "OUT_2") (pintype "passive"))
      (node (ref "U1") (pin "4") (pinfunction "OUT_4") (pintype "passive"))
      (node (ref "U3") (pin "1") (pinfunction "VBAT_1") (pintype "passive"))
      (node (ref "U3") (pin "24") (pinfunction "VDD_1_24") (pintype "passive"))
      (node (ref "U3") (pin "36") (pinfunction "VDD_2_36") (pintype "passive"))
      (node (ref "U3") (pin "48") (pinfunction "VDD_3_48") (pintype "passive"))
      (node (ref "U3") (pin "9") (pinfunction "VDDA_9") (pintype "passive"))
      (node (ref "U4") (pin "10") (pinfunction "RESET_10") (pintype "passive"))
      (node (ref "U4") (pin "16") (pinfunction "VCC_16") (pintype "passive"))
      (node (ref "U5") (pin "10") (pinfunction "RESET_10") (pintype "passive"))
      (node (ref "U5") (pin "16") (pinfunction "VCC_16") (pintype "passive"))
      (node (ref "U6") (pin "10") (pinfunction "RESET_10") (pintype "passive"))
      (node (ref "U6") (pin "16") (pinfunction "VCC_16") (pintype "passive"))
      (node (ref "U7") (pin "10") (pinfunction "RESET_10") (pintype "passive"))
      (node (ref "U7") (pin "16") (pinfunction "VCC_16") (pintype "passive"))
      (node (ref "U8") (pin "10") (pinfunction "RESET_10") (pintype "passive"))
      (node (ref "U8") (pin "16") (pinfunction "VCC_16") (pintype "passive"))
    )
    (net (code "99") (name "unconnected-(U3-PA1-Pad11)") (class "Default")
      (node (ref "U3") (pin "11") (pinfunction "PA1_11") (pintype "passive"))
    )
    (net (code "100") (name "unconnected-(U3-PA2{slash}TX2-Pad12)") (class "Default")
      (node (ref "U3") (pin "12") (pinfunction "PA2/TX2_12") (pintype "passive"))
    )
    (net (code "101") (name "unconnected-(U3-PA3{slash}RX2-Pad13)") (class "Default")
      (node (ref "U3") (pin "13") (pinfunction "PA3/RX2_13") (pintype "passive"))
    )
    (net (code "102") (name "unconnected-(U3-PA4{slash}NSS-Pad14)") (class "Default")
      (node (ref "U3") (pin "14") (pinfunction "PA4/NSS_14") (pintype "passive"))
    )
    (net (code "103") (name "unconnected-(U3-PA5{slash}SCK-Pad15)") (class "Default")
      (node (ref "U3") (pin "15") (pinfunction "PA5/SCK_15") (pintype "passive"))
    )
    (net (code "104") (name "unconnected-(U3-PA6{slash}MISO-Pad16)") (class "Default")
      (node (ref "U3") (pin "16") (pinfunction "PA6/MISO_16") (pintype "passive"))
    )
    (net (code "105") (name "unconnected-(U3-PA7{slash}MOSI-Pad17)") (class "Default")
      (node (ref "U3") (pin "17") (pinfunction "PA7/MOSI_17") (pintype "passive"))
    )
    (net (code "106") (name "unconnected-(U3-PA8-Pad29)") (class "Default")
      (node (ref "U3") (pin "29") (pinfunction "PA8_29") (pintype "passive"))
    )
    (net (code "107") (name "unconnected-(U3-PA9{slash}TX1-Pad30)") (class "Default")
      (node (ref "U3") (pin "30") (pinfunction "PA9/TX1_30") (pintype "passive"))
    )
    (net (code "108") (name "unconnected-(U3-PA10{slash}RX1-Pad31)") (class "Default")
      (node (ref "U3") (pin "31") (pinfunction "PA10/RX1_31") (pintype "passive"))
    )
    (net (code "109") (name "unconnected-(U3-PA11-Pad32)") (class "Default")
      (node (ref "U3") (pin "32") (pinfunction "PA11_32") (pintype "passive"))
    )
    (net (code "110") (name "unconnected-(U3-PA12-Pad33)") (class "Default")
      (node (ref "U3") (pin "33") (pinfunction "PA12_33") (pintype "passive"))
    )
    (net (code "111") (name "unconnected-(U3-PA15-Pad38)") (class "Default")
      (node (ref "U3") (pin "38") (pinfunction "PA15_38") (pintype "passive"))
    )
    (net (code "112") (name "unconnected-(U3-PB0-Pad18)") (class "Default")
      (node (ref "U3") (pin "18") (pinfunction "PB0_18") (pintype "passive"))
    )
    (net (code "113") (name "unconnected-(U3-PB1-Pad19)") (class "Default")
      (node (ref "U3") (pin "19") (pinfunction "PB1_19") (pintype "passive"))
    )
    (net (code "114") (name "unconnected-(U3-PB2-Pad20)") (class "Default")
      (node (ref "U3") (pin "20") (pinfunction "PB2_20") (pintype "passive"))
    )
    (net (code "115") (name "unconnected-(U3-PB3-Pad39)") (class "Default")
      (node (ref "U3") (pin "39") (pinfunction "PB3_39") (pintype "passive"))
    )
    (net (code "116") (name "unconnected-(U3-PB4-Pad40)") (class "Default")
      (node (ref "U3") (pin "40") (pinfunction "PB4_40") (pintype "passive"))
    )
    (net (code "117") (name "unconnected-(U3-PB5-Pad41)") (class "Default")
      (node (ref "U3") (pin "41") (pinfunction "PB5_41") (pintype "passive"))
    )
    (net (code "118") (name "unconnected-(U3-PB6-Pad42)") (class "Default")
      (node (ref "U3") (pin "42") (pinfunction "PB6_42") (pintype "passive"))
    )
    (net (code "119") (name "unconnected-(U3-PB7-Pad43)") (class "Default")
      (node (ref "U3") (pin "43") (pinfunction "PB7_43") (pintype "passive"))
    )
    (net (code "120") (name "unconnected-(U3-PB8-Pad45)") (class "Default")
      (node (ref "U3") (pin "45") (pinfunction "PB8_45") (pintype "passive"))
    )
    (net (code "121") (name "unconnected-(U3-PB9-Pad46)") (class "Default")
      (node (ref "U3") (pin "46") (pinfunction "PB9_46") (pintype "passive"))
    )
    (net (code "122") (name "unconnected-(U3-PB10-Pad21)") (class "Default")
      (node (ref "U3") (pin "21") (pinfunction "PB10_21") (pintype "passive"))
    )
    (net (code "123") (name "unconnected-(U3-PB11-Pad22)") (class "Default")
      (node (ref "U3") (pin "22") (pinfunction "PB11_22") (pintype "passive"))
    )
    (net (code "124") (name "unconnected-(U3-PB15-Pad28)") (class "Default")
      (node (ref "U3") (pin "28") (pinfunction "PB15_28") (pintype "passive"))
    )
    (net (code "125") (name "unconnected-(U3-PC13-Pad2)") (class "Default")
      (node (ref "U3") (pin "2") (pinfunction "PC13_2") (pintype "passive"))
    )
    (net (code "126") (name "unconnected-(U3-PC14-Pad3)") (class "Default")
      (node (ref "U3") (pin "3") (pinfunction "PC14_3") (pintype "passive"))
    )
    (net (code "127") (name "unconnected-(U3-PC15-Pad4)") (class "Default")
      (node (ref "U3") (pin "4") (pinfunction "PC15_4") (pintype "passive"))
    )
    (net (code "128") (name "unconnected-(U4-SQH-Pad9)") (class "Default")
      (node (ref "U4") (pin "9") (pinfunction "SQH_9") (pintype "passive"))
    )
    (net (code "129") (name "unconnected-(Y1-GND-Pad2)") (class "Default")
      (node (ref "Y1") (pin "2") (pinfunction "GND_2") (pintype "passive"))
    )
    (net (code "130") (name "unconnected-(Y1-GND-Pad4)") (class "Default")
      (node (ref "Y1") (pin "4") (pinfunction "GND_4") (pintype "passive"))
    )
  )
)
